# DAPLink.net
KiCad netlist of a schematic drawn in Altium Designer
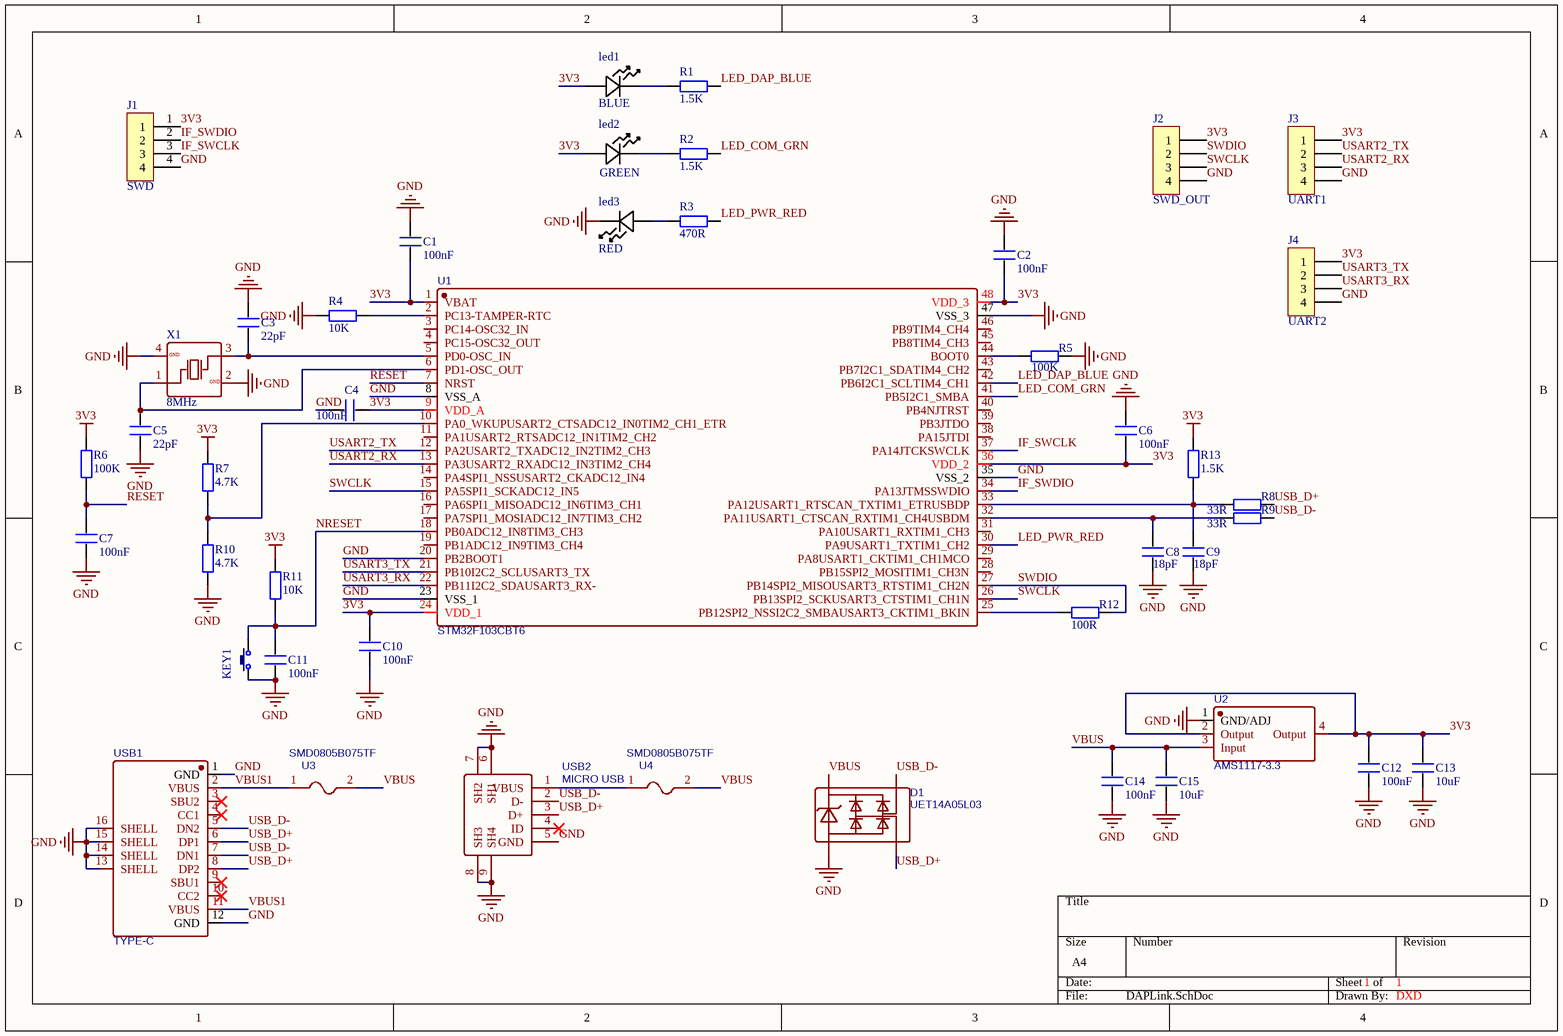
[diagram p0: DAPLink.SchDoc]

(export (version "E")
  (design (tool "Eeschema 10.0.6"))
  (components
    (comp (ref "C1")
      (value "100nF")
      (footprint "0603_CAP")
      (description "无极性贴片电容")
      (fields
        (field (name "MANUFACTURER_PART_NUMBER") "04023A0R3BAT2A")
        (field (name "COPYRIGHT") "Copyright (C) 2016 Accelerated Designs. All rights reserved")
      )
      (libsource (lib "mySchLib") (part "CAP"))
    )
    (comp (ref "C2")
      (value "100nF")
      (footprint "0603_CAP")
      (description "无极性贴片电容")
      (fields
        (field (name "MANUFACTURER_PART_NUMBER") "04023A0R3BAT2A")
        (field (name "COPYRIGHT") "Copyright (C) 2016 Accelerated Designs. All rights reserved")
      )
      (libsource (lib "mySchLib") (part "CAP"))
    )
    (comp (ref "C3")
      (value "22pF")
      (footprint "0603_CAP")
      (description "无极性贴片电容")
      (fields
        (field (name "MANUFACTURER_PART_NUMBER") "04023A0R3BAT2A")
        (field (name "COPYRIGHT") "Copyright (C) 2016 Accelerated Designs. All rights reserved")
      )
      (libsource (lib "mySchLib") (part "CAP"))
    )
    (comp (ref "C4")
      (value "100nF")
      (footprint "0603_CAP")
      (description "无极性贴片电容")
      (fields
        (field (name "MANUFACTURER_PART_NUMBER") "04023A0R3BAT2A")
        (field (name "COPYRIGHT") "Copyright (C) 2016 Accelerated Designs. All rights reserved")
      )
      (libsource (lib "mySchLib") (part "CAP"))
    )
    (comp (ref "C5")
      (value "22pF")
      (footprint "0603_CAP")
      (description "无极性贴片电容")
      (fields
        (field (name "MANUFACTURER_PART_NUMBER") "04023A0R3BAT2A")
        (field (name "COPYRIGHT") "Copyright (C) 2016 Accelerated Designs. All rights reserved")
      )
      (libsource (lib "mySchLib") (part "CAP"))
    )
    (comp (ref "C6")
      (value "100nF")
      (footprint "0603_CAP")
      (description "无极性贴片电容")
      (fields
        (field (name "MANUFACTURER_PART_NUMBER") "04023A0R3BAT2A")
        (field (name "COPYRIGHT") "Copyright (C) 2016 Accelerated Designs. All rights reserved")
      )
      (libsource (lib "mySchLib") (part "CAP"))
    )
    (comp (ref "C7")
      (value "100nF")
      (footprint "0603_CAP")
      (description "无极性贴片电容")
      (fields
        (field (name "MANUFACTURER_PART_NUMBER") "04023A0R3BAT2A")
        (field (name "COPYRIGHT") "Copyright (C) 2016 Accelerated Designs. All rights reserved")
      )
      (libsource (lib "mySchLib") (part "CAP"))
    )
    (comp (ref "C8")
      (value "18pF")
      (footprint "0603_CAP")
      (description "无极性贴片电容")
      (fields
        (field (name "MANUFACTURER_PART_NUMBER") "04023A0R3BAT2A")
        (field (name "COPYRIGHT") "Copyright (C) 2016 Accelerated Designs. All rights reserved")
      )
      (libsource (lib "mySchLib") (part "CAP"))
    )
    (comp (ref "C9")
      (value "18pF")
      (footprint "0603_CAP")
      (description "无极性贴片电容")
      (fields
        (field (name "MANUFACTURER_PART_NUMBER") "04023A0R3BAT2A")
        (field (name "COPYRIGHT") "Copyright (C) 2016 Accelerated Designs. All rights reserved")
      )
      (libsource (lib "mySchLib") (part "CAP"))
    )
    (comp (ref "C10")
      (value "100nF")
      (footprint "0603_CAP")
      (description "无极性贴片电容")
      (fields
        (field (name "MANUFACTURER_PART_NUMBER") "04023A0R3BAT2A")
        (field (name "COPYRIGHT") "Copyright (C) 2016 Accelerated Designs. All rights reserved")
      )
      (libsource (lib "mySchLib") (part "CAP"))
    )
    (comp (ref "C11")
      (value "100nF")
      (footprint "0603_CAP")
      (description "无极性贴片电容")
      (fields
        (field (name "MANUFACTURER_PART_NUMBER") "04023A0R3BAT2A")
        (field (name "COPYRIGHT") "Copyright (C) 2016 Accelerated Designs. All rights reserved")
      )
      (libsource (lib "mySchLib") (part "CAP"))
    )
    (comp (ref "C12")
      (value "100nF")
      (footprint "0603_CAP")
      (description "无极性贴片电容")
      (fields
        (field (name "MANUFACTURER_PART_NUMBER") "04023A0R3BAT2A")
        (field (name "COPYRIGHT") "Copyright (C) 2016 Accelerated Designs. All rights reserved")
      )
      (libsource (lib "mySchLib") (part "CAP"))
    )
    (comp (ref "C13")
      (value "10uF")
      (footprint "0603_CAP")
      (description "无极性贴片电容")
      (fields
        (field (name "MANUFACTURER_PART_NUMBER") "04023A0R3BAT2A")
        (field (name "COPYRIGHT") "Copyright (C) 2016 Accelerated Designs. All rights reserved")
      )
      (libsource (lib "mySchLib") (part "CAP"))
    )
    (comp (ref "C14")
      (value "100nF")
      (footprint "0603_CAP")
      (description "无极性贴片电容")
      (fields
        (field (name "MANUFACTURER_PART_NUMBER") "04023A0R3BAT2A")
        (field (name "COPYRIGHT") "Copyright (C) 2016 Accelerated Designs. All rights reserved")
      )
      (libsource (lib "mySchLib") (part "CAP"))
    )
    (comp (ref "C15")
      (value "10uF")
      (footprint "0603_CAP")
      (description "无极性贴片电容")
      (fields
        (field (name "MANUFACTURER_PART_NUMBER") "04023A0R3BAT2A")
        (field (name "COPYRIGHT") "Copyright (C) 2016 Accelerated Designs. All rights reserved")
      )
      (libsource (lib "mySchLib") (part "CAP"))
    )
    (comp (ref "D1")
      (value "UET14A05L03")
      (footprint "SOT-143")
      (fields (field (name "BOM_SUPPLIER PART") "C78442"))
      (libsource (lib "DAPLink") (part "UET14A05L03"))
    )
    (comp (ref "J1") (value "SWD") (footprint "SWD") (libsource (lib "DAPLink") (part "SWD")))
    (comp (ref "J2")
      (value "SWD_OUT")
      (footprint "XH2.54-4P")
      (description "4P接插件")
      (fields (field (name "MANUFACTURER_PART_NUMBER") "826629-4"))
      (libsource (lib "mySchLib") (part "Header_1x4"))
    )
    (comp (ref "J3")
      (value "UART1")
      (footprint "XH2.54-4P")
      (description "4P接插件")
      (fields (field (name "MANUFACTURER_PART_NUMBER") "826629-4"))
      (libsource (lib "mySchLib") (part "Header_1x4"))
    )
    (comp (ref "J4")
      (value "UART2")
      (footprint "XH2.54-4P")
      (description "4P接插件")
      (fields (field (name "MANUFACTURER_PART_NUMBER") "826629-4"))
      (libsource (lib "mySchLib") (part "Header_1x4"))
    )
    (comp (ref "KEY1")
      (value "KEY")
      (footprint "KEY_TSW-2-2*4*3.5")
      (description "按键")
      (fields (field (name "版权归属") "源创客"))
      (libsource (lib "mySchLib") (part "KEY"))
    )
    (comp (ref "led1")
      (value "BLUE")
      (footprint "0603_LED")
      (description "贴片发光二极管")
      (fields (field (name "MANUFACTURER_PART_NUMBER") "VLMB1310-GS08"))
      (libsource (lib "mySchLib") (part "LED"))
    )
    (comp (ref "led2")
      (value "GREEN")
      (footprint "0603_LED")
      (description "贴片发光二极管")
      (fields (field (name "MANUFACTURER_PART_NUMBER") "VLMB1310-GS08"))
      (libsource (lib "mySchLib") (part "LED"))
    )
    (comp (ref "led3")
      (value "RED")
      (footprint "0603_LED")
      (description "贴片发光二极管")
      (fields (field (name "MANUFACTURER_PART_NUMBER") "VLMB1310-GS08"))
      (libsource (lib "mySchLib") (part "LED"))
    )
    (comp (ref "R1")
      (value "1.5K")
      (footprint "0603_RES")
      (description "贴片电阻")
      (fields (field (name "MANUFACTURER_PART_NUMBER") "RC0402FR-070RL"))
      (libsource (lib "mySchLib") (part "RES"))
    )
    (comp (ref "R2")
      (value "1.5K")
      (footprint "0603_RES")
      (description "贴片电阻")
      (fields (field (name "MANUFACTURER_PART_NUMBER") "RC0402FR-070RL"))
      (libsource (lib "mySchLib") (part "RES"))
    )
    (comp (ref "R3")
      (value "470R")
      (footprint "0603_RES")
      (description "贴片电阻")
      (fields (field (name "MANUFACTURER_PART_NUMBER") "RC0402FR-070RL"))
      (libsource (lib "mySchLib") (part "RES"))
    )
    (comp (ref "R4")
      (value "10K")
      (footprint "0603_RES")
      (description "贴片电阻")
      (fields (field (name "MANUFACTURER_PART_NUMBER") "RC0402FR-070RL"))
      (libsource (lib "mySchLib") (part "RES"))
    )
    (comp (ref "R5")
      (value "100K")
      (footprint "0603_RES")
      (description "贴片电阻")
      (fields (field (name "MANUFACTURER_PART_NUMBER") "RC0402FR-070RL"))
      (libsource (lib "mySchLib") (part "RES"))
    )
    (comp (ref "R6")
      (value "100K")
      (footprint "0603_RES")
      (description "贴片电阻")
      (fields (field (name "MANUFACTURER_PART_NUMBER") "RC0402FR-070RL"))
      (libsource (lib "mySchLib") (part "RES"))
    )
    (comp (ref "R7")
      (value "4.7K")
      (footprint "0603_RES")
      (description "贴片电阻")
      (fields (field (name "MANUFACTURER_PART_NUMBER") "RC0402FR-070RL"))
      (libsource (lib "mySchLib") (part "RES"))
    )
    (comp (ref "R8")
      (value "33R")
      (footprint "0603_RES")
      (description "贴片电阻")
      (fields (field (name "MANUFACTURER_PART_NUMBER") "RC0402FR-070RL"))
      (libsource (lib "mySchLib") (part "RES"))
    )
    (comp (ref "R9")
      (value "33R")
      (footprint "0603_RES")
      (description "贴片电阻")
      (fields (field (name "MANUFACTURER_PART_NUMBER") "RC0402FR-070RL"))
      (libsource (lib "mySchLib") (part "RES"))
    )
    (comp (ref "R10")
      (value "4.7K")
      (footprint "0603_RES")
      (description "贴片电阻")
      (fields (field (name "MANUFACTURER_PART_NUMBER") "RC0402FR-070RL"))
      (libsource (lib "mySchLib") (part "RES"))
    )
    (comp (ref "R11")
      (value "10K")
      (footprint "0603_RES")
      (description "贴片电阻")
      (fields (field (name "MANUFACTURER_PART_NUMBER") "RC0402FR-070RL"))
      (libsource (lib "mySchLib") (part "RES"))
    )
    (comp (ref "R12")
      (value "100R")
      (footprint "0603_RES")
      (description "贴片电阻")
      (fields (field (name "MANUFACTURER_PART_NUMBER") "RC0402FR-070RL"))
      (libsource (lib "mySchLib") (part "RES"))
    )
    (comp (ref "R13")
      (value "1.5K")
      (footprint "0603_RES")
      (description "贴片电阻")
      (fields (field (name "MANUFACTURER_PART_NUMBER") "RC0402FR-070RL"))
      (libsource (lib "mySchLib") (part "RES"))
    )
    (comp (ref "U1")
      (value "STM32F103CBT6")
      (footprint "LQFP-48")
      (fields (field (name "BOM_SUPPLIER PART") "C8304"))
      (libsource (lib "DAPLink") (part "STM32F103CBT6"))
    )
    (comp (ref "U2")
      (value "AMS1117-3.3")
      (footprint "SOT-223")
      (fields (field (name "BOM_SUPPLIER PART") "C369933") (field (name "CONTRIBUTOR") "LCSC"))
      (libsource (lib "mySchLib") (part "AMS1117-3.3"))
    )
    (comp (ref "U3")
      (value "SMD0805B075TF")
      (footprint "F0805")
      (fields (field (name "BOM_SUPPLIER PART") "C269105") (field (name "CONTRIBUTOR") "LCSC"))
      (libsource (lib "DAPLink") (part "SMD0805B075TF"))
    )
    (comp (ref "U4")
      (value "SMD0805B075TF")
      (footprint "F0805")
      (fields (field (name "BOM_SUPPLIER PART") "C269105") (field (name "CONTRIBUTOR") "LCSC"))
      (libsource (lib "DAPLink") (part "SMD0805B075TF"))
    )
    (comp (ref "USB1")
      (value "TYPE-C")
      (footprint "TYPE-C")
      (fields
        (field (name "BOM_SUPPLIER PART") "C530612")
        (field (name "BOM_MANUFACTURER PART") "TYPE-C-31-M-22")
        (field (name "CONTRIBUTOR") "LCSC")
      )
      (libsource (lib "DAPLink") (part "TYPE-C"))
    )
    (comp (ref "USB2")
      (value "MICRO USB")
      (footprint "MICRO-USB")
      (fields
        (field (name "BOM_SUPPLIER PART") "C404968")
        (field (name "BOM_MANUFACTURER PART") "MicroQTJ")
        (field (name "CONTRIBUTOR") "LCSC")
      )
      (libsource (lib "DAPLink") (part "MICRO USB"))
    )
    (comp (ref "X1")
      (value "8MHz")
      (footprint "XTAL-3225-4P")
      (description "4脚无源晶振")
      (libsource (lib "mySchLib") (part "XTAL-4P"))
    )
  )
  (nets
    (net (code "1") (name "/IF_SWCLK") (class "Default")
      (node (ref "J1") (pin "3") (pinfunction "3_3") (pintype "passive"))
      (node (ref "U1") (pin "37") (pinfunction "PA14JTCKSWCLK_37") (pintype "passive"))
    )
    (net (code "2") (name "/IF_SWDIO") (class "Default")
      (node (ref "J1") (pin "2") (pinfunction "2_2") (pintype "passive"))
      (node (ref "U1") (pin "34") (pinfunction "PA13JTMSSWDIO_34") (pintype "passive"))
    )
    (net (code "3") (name "/LED_COM_GRN") (class "Default")
      (node (ref "R2") (pin "2") (pinfunction "2_2") (pintype "passive"))
      (node (ref "U1") (pin "41") (pinfunction "PB5I2C1_SMBA_41") (pintype "passive"))
    )
    (net (code "4") (name "/LED_DAP_BLUE") (class "Default")
      (node (ref "R1") (pin "2") (pinfunction "2_2") (pintype "passive"))
      (node (ref "U1") (pin "42") (pinfunction "PB6I2C1_SCLTIM4_CH1_42") (pintype "passive"))
    )
    (net (code "5") (name "/LED_PWR_RED") (class "Default")
      (node (ref "R3") (pin "2") (pinfunction "2_2") (pintype "passive"))
      (node (ref "U1") (pin "30") (pinfunction "PA9USART1_TXTIM1_CH2_30") (pintype "passive"))
    )
    (net (code "6") (name "/NRESET") (class "Default")
      (node (ref "C11") (pin "2") (pintype "passive"))
      (node (ref "KEY1") (pin "2") (pinfunction "2_2") (pintype "passive"))
      (node (ref "R11") (pin "1") (pinfunction "1_1") (pintype "passive"))
      (node (ref "U1") (pin "18") (pinfunction "PB0ADC12_IN8TIM3_CH3_18") (pintype "passive"))
    )
    (net (code "7") (name "/RESET") (class "Default")
      (node (ref "C7") (pin "2") (pintype "passive"))
      (node (ref "R6") (pin "1") (pinfunction "1_1") (pintype "passive"))
      (node (ref "U1") (pin "7") (pinfunction "NRST_7") (pintype "passive"))
    )
    (net (code "8") (name "/SWCLK") (class "Default")
      (node (ref "J2") (pin "3") (pinfunction "3_3") (pintype "passive"))
      (node (ref "U1") (pin "15") (pinfunction "PA5SPI1_SCKADC12_IN5_15") (pintype "passive"))
      (node (ref "U1") (pin "26") (pinfunction "PB13SPI2_SCKUSART3_CTSTIM1_CH1N_26") (pintype "passive"))
    )
    (net (code "9") (name "/SWDIO") (class "Default")
      (node (ref "J2") (pin "2") (pinfunction "2_2") (pintype "passive"))
      (node (ref "R12") (pin "2") (pinfunction "2_2") (pintype "passive"))
      (node (ref "U1") (pin "27") (pinfunction "PB14SPI2_MISOUSART3_RTSTIM1_CH2N_27") (pintype "passive"))
    )
    (net (code "10") (name "/USART2_RX") (class "Default")
      (node (ref "J3") (pin "3") (pinfunction "3_3") (pintype "passive"))
      (node (ref "U1") (pin "13") (pinfunction "PA3USART2_RXADC12_IN3TIM2_CH4_13") (pintype "passive"))
    )
    (net (code "11") (name "/USART2_TX") (class "Default")
      (node (ref "J3") (pin "2") (pinfunction "2_2") (pintype "passive"))
      (node (ref "U1") (pin "12") (pinfunction "PA2USART2_TXADC12_IN2TIM2_CH3_12") (pintype "passive"))
    )
    (net (code "12") (name "/USART3_RX") (class "Default")
      (node (ref "J4") (pin "3") (pinfunction "3_3") (pintype "passive"))
      (node (ref "U1") (pin "22") (pinfunction "PB11I2C2_SDAUSART3_RX-_22") (pintype "passive"))
    )
    (net (code "13") (name "/USART3_TX") (class "Default")
      (node (ref "J4") (pin "2") (pinfunction "2_2") (pintype "passive"))
      (node (ref "U1") (pin "21") (pinfunction "PB10I2C2_SCLUSART3_TX_21") (pintype "passive"))
    )
    (net (code "14") (name "/USB_D+") (class "Default")
      (node (ref "D1") (pin "2") (pinfunction "2_2") (pintype "passive"))
      (node (ref "R8") (pin "2") (pinfunction "2_2") (pintype "passive"))
      (node (ref "USB1") (pin "6") (pinfunction "DP1_6") (pintype "passive"))
      (node (ref "USB1") (pin "8") (pinfunction "DP2_8") (pintype "passive"))
      (node (ref "USB2") (pin "3") (pinfunction "D+_3") (pintype "passive"))
    )
    (net (code "15") (name "/USB_D-") (class "Default")
      (node (ref "D1") (pin "3") (pinfunction "3_3") (pintype "passive"))
      (node (ref "R9") (pin "2") (pinfunction "2_2") (pintype "passive"))
      (node (ref "USB1") (pin "5") (pinfunction "DN2_5") (pintype "passive"))
      (node (ref "USB1") (pin "7") (pinfunction "DN1_7") (pintype "passive"))
      (node (ref "USB2") (pin "2") (pinfunction "D-_2") (pintype "passive"))
    )
    (net (code "16") (name "/VBUS") (class "Default")
      (node (ref "C14") (pin "2") (pintype "passive"))
      (node (ref "C15") (pin "2") (pintype "passive"))
      (node (ref "D1") (pin "4") (pinfunction "K_4") (pintype "passive"))
      (node (ref "U2") (pin "3") (pinfunction "Input_3") (pintype "passive"))
      (node (ref "U3") (pin "2") (pinfunction "2_2") (pintype "passive"))
      (node (ref "U4") (pin "2") (pinfunction "2_2") (pintype "passive"))
    )
    (net (code "17") (name "/VBUS1") (class "Default")
      (node (ref "U3") (pin "1") (pinfunction "1_1") (pintype "passive"))
      (node (ref "USB1") (pin "11") (pinfunction "VBUS_11") (pintype "passive"))
      (node (ref "USB1") (pin "2") (pinfunction "VBUS_2") (pintype "passive"))
    )
    (net (code "18") (name "3V3") (class "Default")
      (node (ref "C1") (pin "1") (pintype "passive"))
      (node (ref "C10") (pin "2") (pintype "passive"))
      (node (ref "C12") (pin "2") (pintype "passive"))
      (node (ref "C13") (pin "2") (pintype "passive"))
      (node (ref "C2") (pin "1") (pintype "passive"))
      (node (ref "C4") (pin "1") (pintype "passive"))
      (node (ref "C6") (pin "1") (pintype "passive"))
      (node (ref "J1") (pin "1") (pinfunction "1_1") (pintype "passive"))
      (node (ref "J2") (pin "1") (pinfunction "1_1") (pintype "passive"))
      (node (ref "J3") (pin "1") (pinfunction "1_1") (pintype "passive"))
      (node (ref "J4") (pin "1") (pinfunction "1_1") (pintype "passive"))
      (node (ref "R11") (pin "2") (pinfunction "2_2") (pintype "passive"))
      (node (ref "R13") (pin "2") (pinfunction "2_2") (pintype "passive"))
      (node (ref "R6") (pin "2") (pinfunction "2_2") (pintype "passive"))
      (node (ref "R7") (pin "2") (pinfunction "2_2") (pintype "passive"))
      (node (ref "U1") (pin "1") (pinfunction "VBAT_1") (pintype "passive"))
      (node (ref "U1") (pin "24") (pinfunction "VDD_1_24") (pintype "passive"))
      (node (ref "U1") (pin "36") (pinfunction "VDD_2_36") (pintype "passive"))
      (node (ref "U1") (pin "48") (pinfunction "VDD_3_48") (pintype "passive"))
      (node (ref "U1") (pin "9") (pinfunction "VDD_A_9") (pintype "passive"))
      (node (ref "U2") (pin "2") (pinfunction "Output_2") (pintype "passive"))
      (node (ref "U2") (pin "4") (pinfunction "Output_4") (pintype "passive"))
      (node (ref "led1") (pin "2") (pinfunction "2_2") (pintype "passive"))
      (node (ref "led2") (pin "2") (pinfunction "2_2") (pintype "passive"))
    )
    (net (code "19") (name "GND") (class "Default")
      (node (ref "C1") (pin "2") (pintype "passive"))
      (node (ref "C10") (pin "1") (pintype "passive"))
      (node (ref "C11") (pin "1") (pintype "passive"))
      (node (ref "C12") (pin "1") (pintype "passive"))
      (node (ref "C13") (pin "1") (pintype "passive"))
      (node (ref "C14") (pin "1") (pintype "passive"))
      (node (ref "C15") (pin "1") (pintype "passive"))
      (node (ref "C2") (pin "2") (pintype "passive"))
      (node (ref "C3") (pin "2") (pintype "passive"))
      (node (ref "C4") (pin "2") (pintype "passive"))
      (node (ref "C5") (pin "1") (pintype "passive"))
      (node (ref "C6") (pin "2") (pintype "passive"))
      (node (ref "C7") (pin "1") (pintype "passive"))
      (node (ref "C8") (pin "1") (pintype "passive"))
      (node (ref "C9") (pin "1") (pintype "passive"))
      (node (ref "D1") (pin "1") (pinfunction "A_1") (pintype "passive"))
      (node (ref "J1") (pin "4") (pinfunction "4_4") (pintype "passive"))
      (node (ref "J2") (pin "4") (pinfunction "4_4") (pintype "passive"))
      (node (ref "J3") (pin "4") (pinfunction "4_4") (pintype "passive"))
      (node (ref "J4") (pin "4") (pinfunction "4_4") (pintype "passive"))
      (node (ref "KEY1") (pin "1") (pinfunction "1_1") (pintype "passive"))
      (node (ref "R10") (pin "1") (pinfunction "1_1") (pintype "passive"))
      (node (ref "R4") (pin "1") (pinfunction "1_1") (pintype "passive"))
      (node (ref "R5") (pin "2") (pinfunction "2_2") (pintype "passive"))
      (node (ref "U1") (pin "20") (pinfunction "PB2BOOT1_20") (pintype "passive"))
      (node (ref "U1") (pin "23") (pinfunction "VSS_1_23") (pintype "passive"))
      (node (ref "U1") (pin "35") (pinfunction "VSS_2_35") (pintype "passive"))
      (node (ref "U1") (pin "47") (pinfunction "VSS_3_47") (pintype "passive"))
      (node (ref "U1") (pin "8") (pinfunction "VSS_A_8") (pintype "passive"))
      (node (ref "U2") (pin "1") (pinfunction "GND/ADJ_1") (pintype "passive"))
      (node (ref "USB1") (pin "1") (pinfunction "GND_1") (pintype "passive"))
      (node (ref "USB1") (pin "12") (pinfunction "GND_12") (pintype "passive"))
      (node (ref "USB1") (pin "13") (pinfunction "SHELL_13") (pintype "passive"))
      (node (ref "USB1") (pin "14") (pinfunction "SHELL_14") (pintype "passive"))
      (node (ref "USB1") (pin "15") (pinfunction "SHELL_15") (pintype "passive"))
      (node (ref "USB1") (pin "16") (pinfunction "SHELL_16") (pintype "passive"))
      (node (ref "USB2") (pin "5") (pinfunction "GND_5") (pintype "passive"))
      (node (ref "USB2") (pin "6") (pinfunction "SH1_6") (pintype "passive"))
      (node (ref "USB2") (pin "7") (pinfunction "SH2_7") (pintype "passive"))
      (node (ref "USB2") (pin "8") (pinfunction "SH3_8") (pintype "passive"))
      (node (ref "USB2") (pin "9") (pinfunction "SH4_9") (pintype "passive"))
      (node (ref "X1") (pin "2") (pinfunction "GND_2") (pintype "passive"))
      (node (ref "X1") (pin "4") (pinfunction "GND_4") (pintype "passive"))
      (node (ref "led3") (pin "1") (pinfunction "1_1") (pintype "passive"))
    )
    (net (code "20") (name "Net-(R1-Pad1)") (class "Default")
      (node (ref "R1") (pin "1") (pinfunction "1_1") (pintype "passive"))
      (node (ref "led1") (pin "1") (pinfunction "1_1") (pintype "passive"))
    )
    (net (code "21") (name "Net-(R2-Pad1)") (class "Default")
      (node (ref "R2") (pin "1") (pinfunction "1_1") (pintype "passive"))
      (node (ref "led2") (pin "1") (pinfunction "1_1") (pintype "passive"))
    )
    (net (code "22") (name "Net-(R3-Pad1)") (class "Default")
      (node (ref "R3") (pin "1") (pinfunction "1_1") (pintype "passive"))
      (node (ref "led3") (pin "2") (pinfunction "2_2") (pintype "passive"))
    )
    (net (code "23") (name "Net-(U1-BOOT0)") (class "Default")
      (node (ref "R5") (pin "1") (pinfunction "1_1") (pintype "passive"))
      (node (ref "U1") (pin "44") (pinfunction "BOOT0_44") (pintype "passive"))
    )
    (net (code "24") (name "Net-(U1-PA0_WKUPUSART2_CTSADC12_IN0TIM2_CH1_ETR)") (class "Default")
      (node (ref "R10") (pin "2") (pinfunction "2_2") (pintype "passive"))
      (node (ref "R7") (pin "1") (pinfunction "1_1") (pintype "passive"))
      (node (ref "U1") (pin "10") (pinfunction "PA0_WKUPUSART2_CTSADC12_IN0TIM2_CH1_ETR_10") (pintype "passive"))
    )
    (net (code "25") (name "Net-(U1-PA11USART1_CTSCAN_RXTIM1_CH4USBDM)") (class "Default")
      (node (ref "C8") (pin "2") (pintype "passive"))
      (node (ref "R9") (pin "1") (pinfunction "1_1") (pintype "passive"))
      (node (ref "U1") (pin "32") (pinfunction "PA11USART1_CTSCAN_RXTIM1_CH4USBDM_32") (pintype "passive"))
    )
    (net (code "26") (name "Net-(U1-PA12USART1_RTSCAN_TXTIM1_ETRUSBDP)") (class "Default")
      (node (ref "C9") (pin "2") (pintype "passive"))
      (node (ref "R13") (pin "1") (pinfunction "1_1") (pintype "passive"))
      (node (ref "R8") (pin "1") (pinfunction "1_1") (pintype "passive"))
      (node (ref "U1") (pin "33") (pinfunction "PA12USART1_RTSCAN_TXTIM1_ETRUSBDP_33") (pintype "passive"))
    )
    (net (code "27") (name "Net-(U1-PB12SPI2_NSSI2C2_SMBAUSART3_CKTIM1_BKIN)") (class "Default")
      (node (ref "R12") (pin "1") (pinfunction "1_1") (pintype "passive"))
      (node (ref "U1") (pin "25") (pinfunction "PB12SPI2_NSSI2C2_SMBAUSART3_CKTIM1_BKIN_25") (pintype "passive"))
    )
    (net (code "28") (name "Net-(U1-PC13-TAMPER-RTC)") (class "Default")
      (node (ref "R4") (pin "2") (pinfunction "2_2") (pintype "passive"))
      (node (ref "U1") (pin "2") (pinfunction "PC13-TAMPER-RTC_2") (pintype "passive"))
    )
    (net (code "29") (name "Net-(U1-PD0-OSC_IN)") (class "Default")
      (node (ref "C3") (pin "1") (pintype "passive"))
      (node (ref "U1") (pin "5") (pinfunction "PD0-OSC_IN_5") (pintype "passive"))
      (node (ref "X1") (pin "3") (pinfunction "OSC2_3") (pintype "passive"))
    )
    (net (code "30") (name "Net-(U1-PD1-OSC_OUT)") (class "Default")
      (node (ref "C5") (pin "2") (pintype "passive"))
      (node (ref "U1") (pin "6") (pinfunction "PD1-OSC_OUT_6") (pintype "passive"))
      (node (ref "X1") (pin "1") (pinfunction "OSC1_1") (pintype "passive"))
    )
    (net (code "31") (name "Net-(USB2-VBUS)") (class "Default")
      (node (ref "U4") (pin "1") (pinfunction "1_1") (pintype "passive"))
      (node (ref "USB2") (pin "1") (pinfunction "VBUS_1") (pintype "passive"))
    )
    (net (code "32") (name "unconnected-(U1-PA1USART2_RTSADC12_IN1TIM2_CH2-Pad11)") (class "Default")
      (node (ref "U1") (pin "11") (pinfunction "PA1USART2_RTSADC12_IN1TIM2_CH2_11") (pintype "passive"))
    )
    (net (code "33") (name "unconnected-(U1-PA4SPI1_NSSUSART2_CKADC12_IN4-Pad14)") (class "Default")
      (node (ref "U1") (pin "14") (pinfunction "PA4SPI1_NSSUSART2_CKADC12_IN4_14") (pintype "passive"))
    )
    (net (code "34") (name "unconnected-(U1-PA6SPI1_MISOADC12_IN6TIM3_CH1-Pad16)") (class "Default")
      (node (ref "U1") (pin "16") (pinfunction "PA6SPI1_MISOADC12_IN6TIM3_CH1_16") (pintype "passive"))
    )
    (net (code "35") (name "unconnected-(U1-PA7SPI1_MOSIADC12_IN7TIM3_CH2-Pad17)") (class "Default")
      (node (ref "U1") (pin "17") (pinfunction "PA7SPI1_MOSIADC12_IN7TIM3_CH2_17") (pintype "passive"))
    )
    (net (code "36") (name "unconnected-(U1-PA8USART1_CKTIM1_CH1MCO-Pad29)") (class "Default")
      (node (ref "U1") (pin "29") (pinfunction "PA8USART1_CKTIM1_CH1MCO_29") (pintype "passive"))
    )
    (net (code "37") (name "unconnected-(U1-PA10USART1_RXTIM1_CH3-Pad31)") (class "Default")
      (node (ref "U1") (pin "31") (pinfunction "PA10USART1_RXTIM1_CH3_31") (pintype "passive"))
    )
    (net (code "38") (name "unconnected-(U1-PA15JTDI-Pad38)") (class "Default")
      (node (ref "U1") (pin "38") (pinfunction "PA15JTDI_38") (pintype "passive"))
    )
    (net (code "39") (name "unconnected-(U1-PB1ADC12_IN9TIM3_CH4-Pad19)") (class "Default")
      (node (ref "U1") (pin "19") (pinfunction "PB1ADC12_IN9TIM3_CH4_19") (pintype "passive"))
    )
    (net (code "40") (name "unconnected-(U1-PB3JTDO-Pad39)") (class "Default")
      (node (ref "U1") (pin "39") (pinfunction "PB3JTDO_39") (pintype "passive"))
    )
    (net (code "41") (name "unconnected-(U1-PB4NJTRST-Pad40)") (class "Default")
      (node (ref "U1") (pin "40") (pinfunction "PB4NJTRST_40") (pintype "passive"))
    )
    (net (code "42") (name "unconnected-(U1-PB7I2C1_SDATIM4_CH2-Pad43)") (class "Default")
      (node (ref "U1") (pin "43") (pinfunction "PB7I2C1_SDATIM4_CH2_43") (pintype "passive"))
    )
    (net (code "43") (name "unconnected-(U1-PB8TIM4_CH3-Pad45)") (class "Default")
      (node (ref "U1") (pin "45") (pinfunction "PB8TIM4_CH3_45") (pintype "passive"))
    )
    (net (code "44") (name "unconnected-(U1-PB9TIM4_CH4-Pad46)") (class "Default")
      (node (ref "U1") (pin "46") (pinfunction "PB9TIM4_CH4_46") (pintype "passive"))
    )
    (net (code "45") (name "unconnected-(U1-PB15SPI2_MOSITIM1_CH3N-Pad28)") (class "Default")
      (node (ref "U1") (pin "28") (pinfunction "PB15SPI2_MOSITIM1_CH3N_28") (pintype "passive"))
    )
    (net (code "46") (name "unconnected-(U1-PC14-OSC32_IN-Pad3)") (class "Default")
      (node (ref "U1") (pin "3") (pinfunction "PC14-OSC32_IN_3") (pintype "passive"))
    )
    (net (code "47") (name "unconnected-(U1-PC15-OSC32_OUT-Pad4)") (class "Default")
      (node (ref "U1") (pin "4") (pinfunction "PC15-OSC32_OUT_4") (pintype "passive"))
    )
    (net (code "48") (name "unconnected-(USB1-CC1-Pad4)") (class "Default")
      (node (ref "USB1") (pin "4") (pinfunction "CC1_4") (pintype "passive+no_connect"))
    )
    (net (code "49") (name "unconnected-(USB1-CC2-Pad10)") (class "Default")
      (node (ref "USB1") (pin "10") (pinfunction "CC2_10") (pintype "passive+no_connect"))
    )
    (net (code "50") (name "unconnected-(USB1-SBU1-Pad9)") (class "Default")
      (node (ref "USB1") (pin "9") (pinfunction "SBU1_9") (pintype "passive+no_connect"))
    )
    (net (code "51") (name "unconnected-(USB1-SBU2-Pad3)") (class "Default")
      (node (ref "USB1") (pin "3") (pinfunction "SBU2_3") (pintype "passive+no_connect"))
    )
    (net (code "52") (name "unconnected-(USB2-ID-Pad4)") (class "Default")
      (node (ref "USB2") (pin "4") (pinfunction "ID_4") (pintype "passive+no_connect"))
    )
  )
)
